# RS232_M_V1.net
KiCad netlist of a schematic drawn in Altium Designer
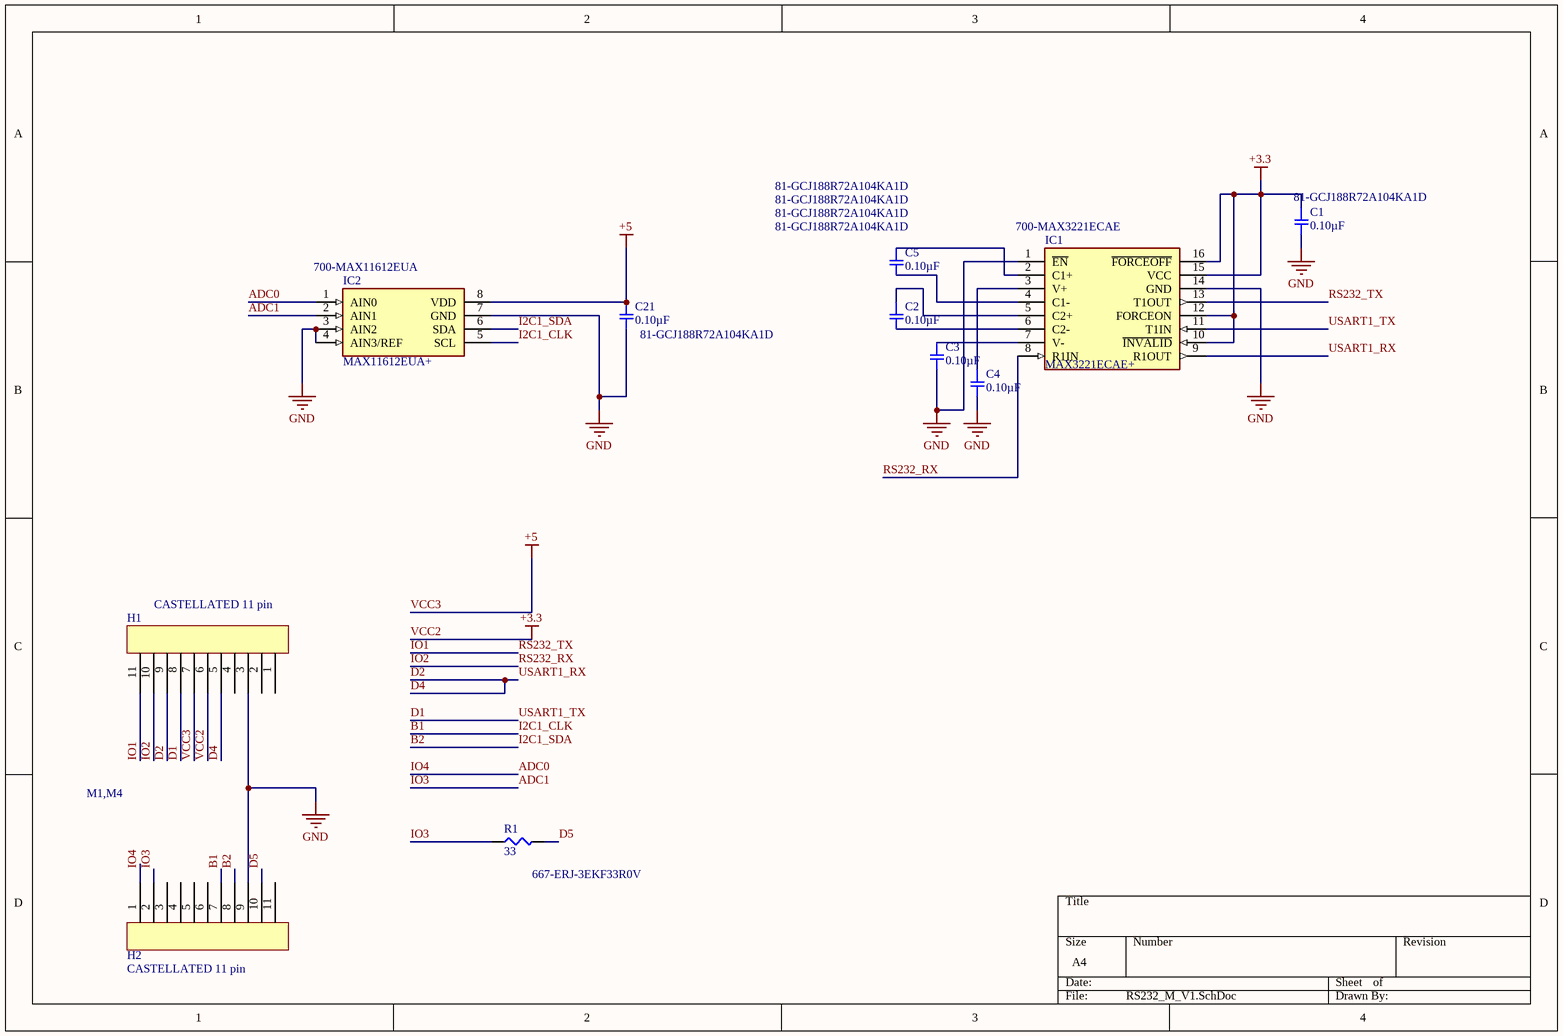
[diagram p0: RS232_M_V1.SchDoc]

(export (version "E")
  (design (tool "Eeschema 10.0.6"))
  (components
    (comp (ref "C1")
      (value "0.10µF")
      (footprint "SMD-0603C")
      (description "CAP CER 0.1UF 100V X7R 0603")
      (fields
        (field (name "PART NUMBER") "GCJ188R72A104KA01D")
        (field (name "DIGI-KEY PART NUMBER") "490-13420-1-ND")
        (field (name "SUPPLIER PART NUMBER 1") "81-GCJ188R72A104KA1D")
      )
      (libsource (lib "cap_murata") (part "CAPACITOR"))
    )
    (comp (ref "C2")
      (value "0.10µF")
      (footprint "SMD-0603C")
      (description "CAP CER 0.1UF 100V X7R 0603")
      (fields
        (field (name "PART NUMBER") "GCJ188R72A104KA01D")
        (field (name "DIGI-KEY PART NUMBER") "490-13420-1-ND")
        (field (name "SUPPLIER PART NUMBER 1") "81-GCJ188R72A104KA1D")
      )
      (libsource (lib "cap_murata") (part "CAPACITOR"))
    )
    (comp (ref "C3")
      (value "0.10µF")
      (footprint "SMD-0603C")
      (description "CAP CER 0.1UF 100V X7R 0603")
      (fields
        (field (name "PART NUMBER") "GCJ188R72A104KA01D")
        (field (name "DIGI-KEY PART NUMBER") "490-13420-1-ND")
        (field (name "SUPPLIER PART NUMBER 1") "81-GCJ188R72A104KA1D")
      )
      (libsource (lib "cap_murata") (part "CAPACITOR"))
    )
    (comp (ref "C4")
      (value "0.10µF")
      (footprint "SMD-0603C")
      (description "CAP CER 0.1UF 100V X7R 0603")
      (fields
        (field (name "PART NUMBER") "GCJ188R72A104KA01D")
        (field (name "DIGI-KEY PART NUMBER") "490-13420-1-ND")
        (field (name "SUPPLIER PART NUMBER 1") "81-GCJ188R72A104KA1D")
      )
      (libsource (lib "cap_murata") (part "CAPACITOR"))
    )
    (comp (ref "C5")
      (value "0.10µF")
      (footprint "SMD-0603C")
      (description "CAP CER 0.1UF 100V X7R 0603")
      (fields
        (field (name "PART NUMBER") "GCJ188R72A104KA01D")
        (field (name "DIGI-KEY PART NUMBER") "490-13420-1-ND")
        (field (name "SUPPLIER PART NUMBER 1") "81-GCJ188R72A104KA1D")
      )
      (libsource (lib "cap_murata") (part "CAPACITOR"))
    )
    (comp (ref "C21")
      (value "0.10µF")
      (footprint "SMD-0603C")
      (description "CAP CER 0.1UF 100V X7R 0603")
      (fields
        (field (name "PART NUMBER") "GCJ188R72A104KA01D")
        (field (name "DIGI-KEY PART NUMBER") "490-13420-1-ND")
        (field (name "SUPPLIER PART NUMBER 1") "81-GCJ188R72A104KA1D")
      )
      (libsource (lib "cap_murata") (part "CAPACITOR"))
    )
    (comp (ref "H1")
      (value "CASTELLATED 11 pin")
      (footprint "CASTELLATED 11 pin")
      (libsource (lib "") (part "CASTELLATED 11 pin_1"))
    )
    (comp (ref "H2")
      (value "CASTELLATED 11 pin")
      (footprint "CASTELLATED 11 pin")
      (libsource (lib "USIB") (part "CASTELLATED 11 pin"))
    )
    (comp (ref "IC1")
      (value "MAX3221ECAE+")
      (footprint "SamacSys:SOP65P778X199-16N")
      (description "Integrated Circuit")
      (fields (field (name "SUPPLIER PART NUMBER 1") "700-MAX3221ECAE"))
      (libsource (lib "*") (part "MAX3221ECAE+"))
    )
    (comp (ref "IC2")
      (value "MAX11612EUA+")
      (footprint "SOP65P490X110-8N")
      (description "Integrated Circuit")
      (fields (field (name "SUPPLIER PART NUMBER 1") "700-MAX11612EUA"))
      (libsource (lib "SamacSys") (part "MAX11612EUA+"))
    )
    (comp (ref "R1")
      (value "33")
      (footprint "SMD-0603-RES")
      (description "RES SMD 33 OHM 1% 1/10W 0603")
      (fields
        (field (name "PART NUMBER") "ERJ-3EKF33R0V")
        (field (name "DIGI-KEY PART NUMBER") "P33.0HCT-ND")
        (field (name "SUPPLIER PART NUMBER 1") "667-ERJ-3EKF33R0V")
      )
      (libsource (lib "Panasonic_ERJ_0603") (part "ERJ-3EKF33R0V"))
    )
  )
  (nets
    (net (code "1") (name "+3.3") (class "Default")
      (node (ref "C1") (pin "1") (pinfunction "1_1") (pintype "passive"))
      (node (ref "H1") (pin "6") (pintype "passive"))
      (node (ref "IC1") (pin "10") (pinfunction "~{INVALID}_10") (pintype "input"))
      (node (ref "IC1") (pin "12") (pinfunction "FORCEON_12") (pintype "passive"))
      (node (ref "IC1") (pin "15") (pinfunction "VCC_15") (pintype "power_in"))
      (node (ref "IC1") (pin "16") (pinfunction "~{FORCEOFF}_16") (pintype "passive"))
    )
    (net (code "2") (name "+5") (class "Default")
      (node (ref "C21") (pin "1") (pinfunction "1_1") (pintype "passive"))
      (node (ref "H1") (pin "7") (pintype "passive"))
      (node (ref "IC2") (pin "8") (pinfunction "VDD_8") (pintype "power_in"))
    )
    (net (code "3") (name "/ADC0") (class "Default")
      (node (ref "H2") (pin "1") (pintype "passive"))
      (node (ref "IC2") (pin "1") (pinfunction "AIN0_1") (pintype "input"))
    )
    (net (code "4") (name "/ADC1") (class "Default")
      (node (ref "H2") (pin "2") (pintype "passive"))
      (node (ref "IC2") (pin "2") (pinfunction "AIN1_2") (pintype "input"))
      (node (ref "R1") (pin "1") (pinfunction "1_1") (pintype "passive"))
    )
    (net (code "5") (name "/B1") (class "Default")
      (node (ref "H2") (pin "7") (pintype "passive"))
      (node (ref "IC2") (pin "5") (pinfunction "SCL_5") (pintype "passive"))
    )
    (net (code "6") (name "/B2") (class "Default")
      (node (ref "H2") (pin "8") (pintype "passive"))
      (node (ref "IC2") (pin "6") (pinfunction "SDA_6") (pintype "passive"))
    )
    (net (code "7") (name "/D1") (class "Default")
      (node (ref "H1") (pin "8") (pintype "passive"))
      (node (ref "IC1") (pin "11") (pinfunction "T1IN_11") (pintype "input"))
    )
    (net (code "8") (name "/D2") (class "Default")
      (node (ref "H1") (pin "5") (pintype "passive"))
      (node (ref "H1") (pin "9") (pintype "passive"))
      (node (ref "IC1") (pin "9") (pinfunction "R1OUT_9") (pintype "output"))
    )
    (net (code "9") (name "/D5") (class "Default")
      (node (ref "H2") (pin "10") (pintype "passive"))
      (node (ref "R1") (pin "2") (pinfunction "2_2") (pintype "passive"))
    )
    (net (code "10") (name "/IO1") (class "Default")
      (node (ref "H1") (pin "11") (pintype "passive"))
      (node (ref "IC1") (pin "13") (pinfunction "T1OUT_13") (pintype "output"))
    )
    (net (code "11") (name "/IO2") (class "Default")
      (node (ref "H1") (pin "10") (pintype "passive"))
      (node (ref "IC1") (pin "8") (pinfunction "R1IN_8") (pintype "input"))
    )
    (net (code "12") (name "GND") (class "Default")
      (node (ref "C1") (pin "2") (pinfunction "2_2") (pintype "passive"))
      (node (ref "C21") (pin "2") (pinfunction "2_2") (pintype "passive"))
      (node (ref "C3") (pin "2") (pinfunction "2_2") (pintype "passive"))
      (node (ref "C4") (pin "2") (pinfunction "2_2") (pintype "passive"))
      (node (ref "H1") (pin "3") (pintype "passive"))
      (node (ref "H2") (pin "9") (pintype "passive"))
      (node (ref "IC1") (pin "1") (pinfunction "~{EN}_1") (pintype "passive"))
      (node (ref "IC1") (pin "14") (pinfunction "GND_14") (pintype "power_in"))
      (node (ref "IC2") (pin "3") (pinfunction "AIN2_3") (pintype "input"))
      (node (ref "IC2") (pin "4") (pinfunction "AIN3/REF_4") (pintype "input"))
      (node (ref "IC2") (pin "7") (pinfunction "GND_7") (pintype "power_in"))
    )
    (net (code "13") (name "Net-(IC1-C1+)") (class "Default")
      (node (ref "C5") (pin "1") (pinfunction "1_1") (pintype "passive"))
      (node (ref "IC1") (pin "2") (pinfunction "C1+_2") (pintype "passive"))
    )
    (net (code "14") (name "Net-(IC1-C1-)") (class "Default")
      (node (ref "C5") (pin "2") (pinfunction "2_2") (pintype "passive"))
      (node (ref "IC1") (pin "4") (pinfunction "C1-_4") (pintype "passive"))
    )
    (net (code "15") (name "Net-(IC1-C2+)") (class "Default")
      (node (ref "C2") (pin "1") (pinfunction "1_1") (pintype "passive"))
      (node (ref "IC1") (pin "5") (pinfunction "C2+_5") (pintype "passive"))
    )
    (net (code "16") (name "Net-(IC1-C2-)") (class "Default")
      (node (ref "C2") (pin "2") (pinfunction "2_2") (pintype "passive"))
      (node (ref "IC1") (pin "6") (pinfunction "C2-_6") (pintype "passive"))
    )
    (net (code "17") (name "Net-(IC1-V+)") (class "Default")
      (node (ref "C4") (pin "1") (pinfunction "1_1") (pintype "passive"))
      (node (ref "IC1") (pin "3") (pinfunction "V+_3") (pintype "passive"))
    )
    (net (code "18") (name "Net-(IC1-V-)") (class "Default")
      (node (ref "C3") (pin "1") (pinfunction "1_1") (pintype "passive"))
      (node (ref "IC1") (pin "7") (pinfunction "V-_7") (pintype "passive"))
    )
    (net (code "19") (name "unconnected-(H1-Pad1)") (class "Default")
      (node (ref "H1") (pin "1") (pintype "passive"))
    )
    (net (code "20") (name "unconnected-(H1-Pad2)") (class "Default")
      (node (ref "H1") (pin "2") (pintype "passive"))
    )
    (net (code "21") (name "unconnected-(H1-Pad4)") (class "Default")
      (node (ref "H1") (pin "4") (pintype "passive"))
    )
    (net (code "22") (name "unconnected-(H2-Pad3)") (class "Default")
      (node (ref "H2") (pin "3") (pintype "passive"))
    )
    (net (code "23") (name "unconnected-(H2-Pad4)") (class "Default")
      (node (ref "H2") (pin "4") (pintype "passive"))
    )
    (net (code "24") (name "unconnected-(H2-Pad5)") (class "Default")
      (node (ref "H2") (pin "5") (pintype "passive"))
    )
    (net (code "25") (name "unconnected-(H2-Pad6)") (class "Default")
      (node (ref "H2") (pin "6") (pintype "passive"))
    )
    (net (code "26") (name "unconnected-(H2-Pad11)") (class "Default")
      (node (ref "H2") (pin "11") (pintype "passive"))
    )
  )
)
